# basic_pos_neg_v0001.net
KiCad netlist of a schematic drawn in EAGLE
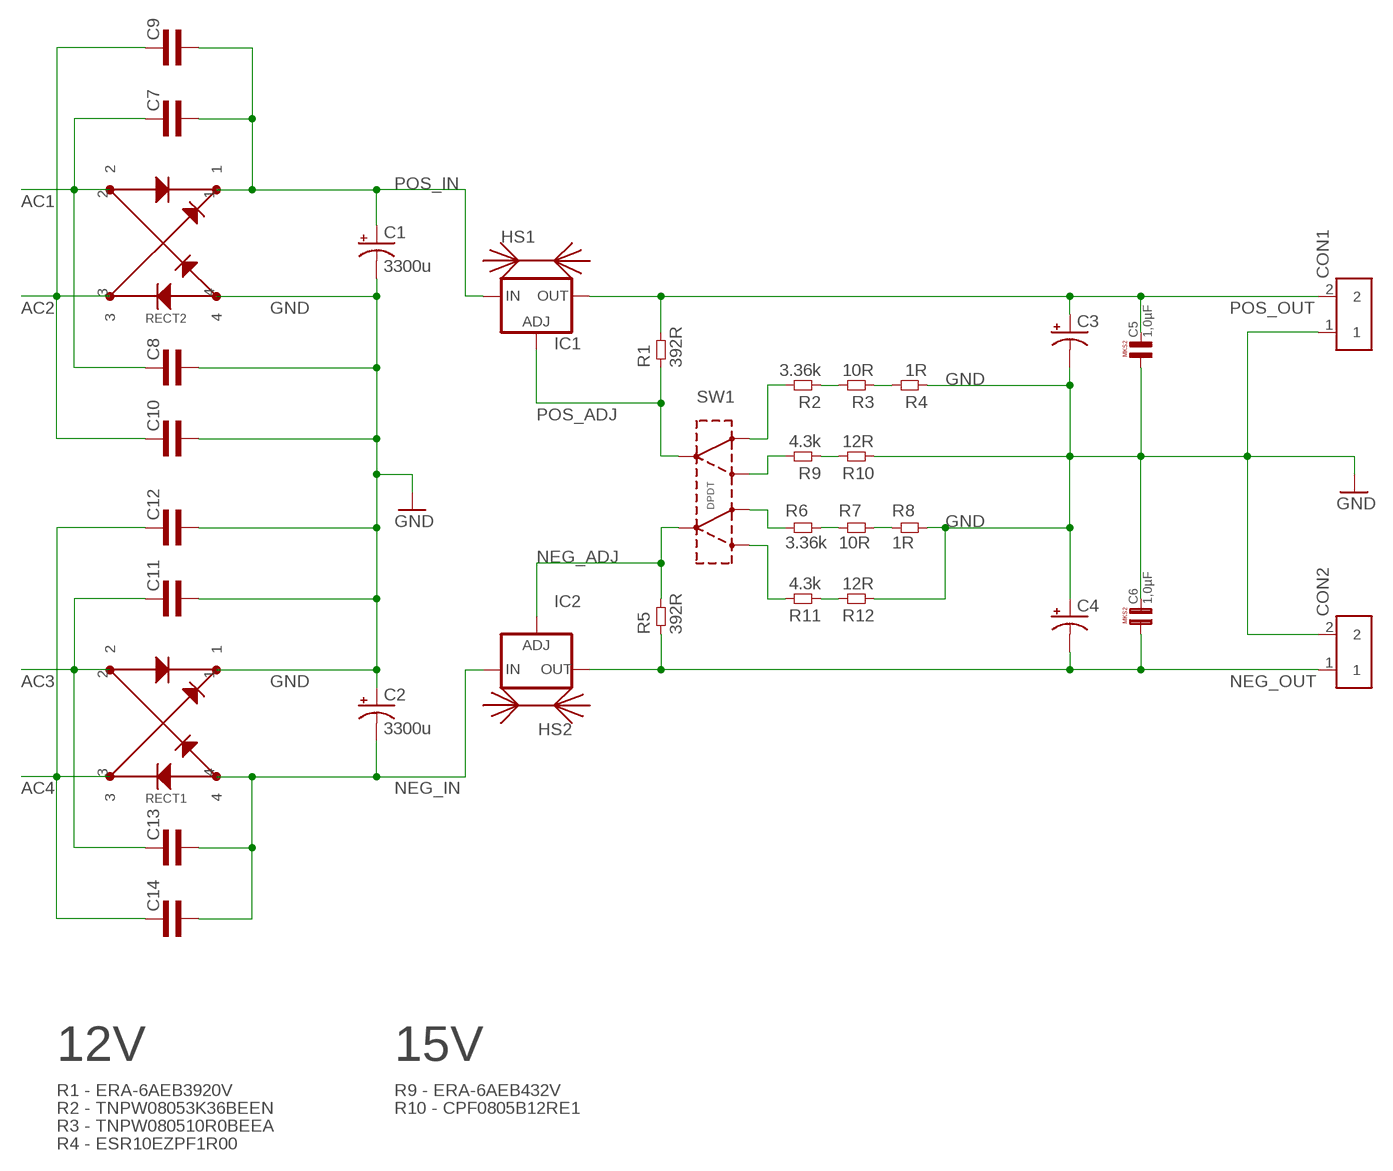
[diagram p0: schematic, sheet 1]

(export (version "E")
  (design (tool "Eeschema 10.0.6"))
  (components
    (comp (ref "C1")
      (value "3300u")
      (footprint "eagle-import:E7,5-18")
      (libsource (lib "eagle-import") (part "CPOL-USE7.5-18"))
    )
    (comp (ref "C2")
      (value "3300u")
      (footprint "eagle-import:E7,5-18")
      (libsource (lib "eagle-import") (part "CPOL-USE7.5-18"))
    )
    (comp (ref "C3")
      (value "CPOL-USE3.5-8")
      (footprint "eagle-import:E3,5-8")
      (libsource (lib "eagle-import") (part "CPOL-USE3.5-8"))
    )
    (comp (ref "C4")
      (value "CPOL-USE3.5-8")
      (footprint "eagle-import:E3,5-8")
      (libsource (lib "eagle-import") (part "CPOL-USE3.5-8"))
    )
    (comp (ref "C5")
      (value "1,0µF")
      (footprint "eagle-import:R5B5")
      (libsource (lib "eagle-import") (part "1,0µF"))
    )
    (comp (ref "C6")
      (value "1,0µF")
      (footprint "eagle-import:R5B5")
      (libsource (lib "eagle-import") (part "1,0µF"))
    )
    (comp (ref "C7")
      (value "CAP0805L3")
      (footprint "eagle-import:0805L3")
      (libsource (lib "eagle-import") (part "CAP0805L3"))
    )
    (comp (ref "C8")
      (value "CAP0805L3")
      (footprint "eagle-import:0805L3")
      (libsource (lib "eagle-import") (part "CAP0805L3"))
    )
    (comp (ref "C9")
      (value "CAP0805L3")
      (footprint "eagle-import:0805L3")
      (libsource (lib "eagle-import") (part "CAP0805L3"))
    )
    (comp (ref "C10")
      (value "CAP0805L3")
      (footprint "eagle-import:0805L3")
      (libsource (lib "eagle-import") (part "CAP0805L3"))
    )
    (comp (ref "C11")
      (value "CAP0805L3")
      (footprint "eagle-import:0805L3")
      (libsource (lib "eagle-import") (part "CAP0805L3"))
    )
    (comp (ref "C12")
      (value "CAP0805L3")
      (footprint "eagle-import:0805L3")
      (libsource (lib "eagle-import") (part "CAP0805L3"))
    )
    (comp (ref "C13")
      (value "CAP0805L3")
      (footprint "eagle-import:0805L3")
      (libsource (lib "eagle-import") (part "CAP0805L3"))
    )
    (comp (ref "C14")
      (value "CAP0805L3")
      (footprint "eagle-import:0805L3")
      (libsource (lib "eagle-import") (part "CAP0805L3"))
    )
    (comp (ref "CON1")
      (value "TERM_BLOCK_2")
      (footprint "eagle-import:TERM_BLOCK_2")
      (libsource (lib "eagle-import") (part "TERM_BLOCK_2"))
    )
    (comp (ref "CON2")
      (value "TERM_BLOCK_2")
      (footprint "eagle-import:TERM_BLOCK_2")
      (libsource (lib "eagle-import") (part "TERM_BLOCK_2"))
    )
    (comp (ref "HS1")
      (value "HEATSINKTO-220-R")
      (footprint "eagle-import:HEATSINK-TO-220-R")
      (libsource (lib "eagle-import") (part "HEATSINKTO-220-R"))
    )
    (comp (ref "HS2")
      (value "HEATSINKTO-220-R")
      (footprint "eagle-import:HEATSINK-TO-220-R")
      (libsource (lib "eagle-import") (part "HEATSINKTO-220-R"))
    )
    (comp (ref "IC1")
      (value "LM317TS")
      (footprint "eagle-import:317TS")
      (libsource (lib "eagle-import") (part "LM317TS"))
    )
    (comp (ref "IC2")
      (value "LM337TS")
      (footprint "eagle-import:337TS")
      (libsource (lib "eagle-import") (part "LM337TS"))
    )
    (comp (ref "R1")
      (value "392R")
      (footprint "eagle-import:0805L3")
      (libsource (lib "eagle-import") (part "RES0805L3"))
    )
    (comp (ref "R2")
      (value "3.36k")
      (footprint "eagle-import:0805L3")
      (libsource (lib "eagle-import") (part "RES0805L3"))
    )
    (comp (ref "R3")
      (value "10R")
      (footprint "eagle-import:0805L3")
      (libsource (lib "eagle-import") (part "RES0805L3"))
    )
    (comp (ref "R4")
      (value "1R")
      (footprint "eagle-import:0805L3")
      (libsource (lib "eagle-import") (part "RES0805L3"))
    )
    (comp (ref "R5")
      (value "392R")
      (footprint "eagle-import:0805L3")
      (libsource (lib "eagle-import") (part "RES0805L3"))
    )
    (comp (ref "R6")
      (value "3.36k")
      (footprint "eagle-import:0805L3")
      (libsource (lib "eagle-import") (part "RES0805L3"))
    )
    (comp (ref "R7")
      (value "10R")
      (footprint "eagle-import:0805L3")
      (libsource (lib "eagle-import") (part "RES0805L3"))
    )
    (comp (ref "R8")
      (value "1R")
      (footprint "eagle-import:0805L3")
      (libsource (lib "eagle-import") (part "RES0805L3"))
    )
    (comp (ref "R9")
      (value "4.3k")
      (footprint "eagle-import:0805L3")
      (libsource (lib "eagle-import") (part "RES0805L3"))
    )
    (comp (ref "R10")
      (value "12R")
      (footprint "eagle-import:0805L3")
      (libsource (lib "eagle-import") (part "RES0805L3"))
    )
    (comp (ref "R11")
      (value "4.3k")
      (footprint "eagle-import:0805L3")
      (libsource (lib "eagle-import") (part "RES0805L3"))
    )
    (comp (ref "R12")
      (value "12R")
      (footprint "eagle-import:0805L3")
      (libsource (lib "eagle-import") (part "RES0805L3"))
    )
    (comp (ref "RECT1")
      (value "RECTIFIER_Z4GP206")
      (footprint "eagle-import:RECTIFIER_ABS-4")
      (libsource (lib "eagle-import") (part "RECTIFIER_Z4GP206"))
    )
    (comp (ref "RECT2")
      (value "RECTIFIER_Z4GP206")
      (footprint "eagle-import:RECTIFIER_ABS-4")
      (libsource (lib "eagle-import") (part "RECTIFIER_Z4GP206"))
    )
    (comp (ref "SW1")
      (value "DPDT")
      (footprint "eagle-import:WIRES-2X6-14G")
      (libsource (lib "eagle-import") (part "DPDT"))
    )
  )
  (nets
    (net (code "1") (name "/AC1") (class "Default")
      (node (ref "C7") (pin "1") (pinfunction "1_1") (pintype "bidirectional"))
      (node (ref "C8") (pin "1") (pinfunction "1_1") (pintype "bidirectional"))
      (node (ref "RECT2") (pin "2") (pinfunction "2_2") (pintype "bidirectional"))
    )
    (net (code "2") (name "/AC2") (class "Default")
      (node (ref "C10") (pin "1") (pinfunction "1_1") (pintype "bidirectional"))
      (node (ref "C9") (pin "1") (pinfunction "1_1") (pintype "bidirectional"))
      (node (ref "RECT2") (pin "3") (pinfunction "3_3") (pintype "bidirectional"))
    )
    (net (code "3") (name "/AC3") (class "Default")
      (node (ref "C11") (pin "1") (pinfunction "1_1") (pintype "bidirectional"))
      (node (ref "C13") (pin "1") (pinfunction "1_1") (pintype "bidirectional"))
      (node (ref "RECT1") (pin "2") (pinfunction "2_2") (pintype "bidirectional"))
    )
    (net (code "4") (name "/AC4") (class "Default")
      (node (ref "C12") (pin "1") (pinfunction "1_1") (pintype "bidirectional"))
      (node (ref "C14") (pin "1") (pinfunction "1_1") (pintype "bidirectional"))
      (node (ref "RECT1") (pin "3") (pinfunction "3_3") (pintype "bidirectional"))
    )
    (net (code "5") (name "/NEG_ADJ") (class "Default")
      (node (ref "IC2") (pin "1") (pinfunction "ADJ_1") (pintype "input"))
      (node (ref "R5") (pin "2") (pinfunction "2_2") (pintype "bidirectional"))
      (node (ref "SW1") (pin "5") (pinfunction "INB_5") (pintype "bidirectional"))
    )
    (net (code "6") (name "/NEG_IN") (class "Default")
      (node (ref "C13") (pin "2") (pinfunction "2_2") (pintype "bidirectional"))
      (node (ref "C14") (pin "2") (pinfunction "2_2") (pintype "bidirectional"))
      (node (ref "C2") (pin "-") (pinfunction "-_-") (pintype "passive"))
      (node (ref "IC2") (pin "2") (pinfunction "IN_2") (pintype "input"))
      (node (ref "RECT1") (pin "4") (pinfunction "4_4") (pintype "bidirectional"))
    )
    (net (code "7") (name "/NEG_OUT") (class "Default")
      (node (ref "C4") (pin "-") (pinfunction "-_-") (pintype "passive"))
      (node (ref "C6") (pin "1") (pinfunction "1_1") (pintype "passive"))
      (node (ref "CON2") (pin "1") (pinfunction "1_1") (pintype "bidirectional"))
      (node (ref "IC2") (pin "3") (pinfunction "OUT_3") (pintype "passive"))
      (node (ref "R5") (pin "1") (pinfunction "1_1") (pintype "bidirectional"))
    )
    (net (code "8") (name "/POS_ADJ") (class "Default")
      (node (ref "IC1") (pin "1") (pinfunction "ADJ_1") (pintype "input"))
      (node (ref "R1") (pin "1") (pinfunction "1_1") (pintype "bidirectional"))
      (node (ref "SW1") (pin "2") (pinfunction "INA_2") (pintype "bidirectional"))
    )
    (net (code "9") (name "/POS_IN") (class "Default")
      (node (ref "C1") (pin "+") (pinfunction "+_+") (pintype "passive"))
      (node (ref "C7") (pin "2") (pinfunction "2_2") (pintype "bidirectional"))
      (node (ref "C9") (pin "2") (pinfunction "2_2") (pintype "bidirectional"))
      (node (ref "IC1") (pin "3") (pinfunction "IN_3") (pintype "input"))
      (node (ref "RECT2") (pin "1") (pinfunction "1_1") (pintype "bidirectional"))
    )
    (net (code "10") (name "/POS_OUT") (class "Default")
      (node (ref "C3") (pin "+") (pinfunction "+_+") (pintype "passive"))
      (node (ref "C5") (pin "2") (pinfunction "2_2") (pintype "passive"))
      (node (ref "CON1") (pin "2") (pinfunction "2_2") (pintype "bidirectional"))
      (node (ref "IC1") (pin "2") (pinfunction "OUT_2") (pintype "passive"))
      (node (ref "R1") (pin "2") (pinfunction "2_2") (pintype "bidirectional"))
    )
    (net (code "11") (name "GND") (class "Default")
      (node (ref "C1") (pin "-") (pinfunction "-_-") (pintype "passive"))
      (node (ref "C10") (pin "2") (pinfunction "2_2") (pintype "bidirectional"))
      (node (ref "C11") (pin "2") (pinfunction "2_2") (pintype "bidirectional"))
      (node (ref "C12") (pin "2") (pinfunction "2_2") (pintype "bidirectional"))
      (node (ref "C2") (pin "+") (pinfunction "+_+") (pintype "passive"))
      (node (ref "C3") (pin "-") (pinfunction "-_-") (pintype "passive"))
      (node (ref "C4") (pin "+") (pinfunction "+_+") (pintype "passive"))
      (node (ref "C5") (pin "1") (pinfunction "1_1") (pintype "passive"))
      (node (ref "C6") (pin "2") (pinfunction "2_2") (pintype "passive"))
      (node (ref "C8") (pin "2") (pinfunction "2_2") (pintype "bidirectional"))
      (node (ref "CON1") (pin "1") (pinfunction "1_1") (pintype "bidirectional"))
      (node (ref "CON2") (pin "2") (pinfunction "2_2") (pintype "bidirectional"))
      (node (ref "R10") (pin "1") (pinfunction "1_1") (pintype "bidirectional"))
      (node (ref "R12") (pin "1") (pinfunction "1_1") (pintype "bidirectional"))
      (node (ref "R4") (pin "1") (pinfunction "1_1") (pintype "bidirectional"))
      (node (ref "R8") (pin "2") (pinfunction "2_2") (pintype "bidirectional"))
      (node (ref "RECT1") (pin "1") (pinfunction "1_1") (pintype "bidirectional"))
      (node (ref "RECT2") (pin "4") (pinfunction "4_4") (pintype "bidirectional"))
    )
    (net (code "12") (name "Net-(R2-Pad1)") (class "Default")
      (node (ref "R2") (pin "1") (pinfunction "1_1") (pintype "bidirectional"))
      (node (ref "R3") (pin "2") (pinfunction "2_2") (pintype "bidirectional"))
    )
    (net (code "13") (name "Net-(R3-Pad1)") (class "Default")
      (node (ref "R3") (pin "1") (pinfunction "1_1") (pintype "bidirectional"))
      (node (ref "R4") (pin "2") (pinfunction "2_2") (pintype "bidirectional"))
    )
    (net (code "14") (name "Net-(R6-Pad2)") (class "Default")
      (node (ref "R6") (pin "2") (pinfunction "2_2") (pintype "bidirectional"))
      (node (ref "R7") (pin "1") (pinfunction "1_1") (pintype "bidirectional"))
    )
    (net (code "15") (name "Net-(R7-Pad2)") (class "Default")
      (node (ref "R7") (pin "2") (pinfunction "2_2") (pintype "bidirectional"))
      (node (ref "R8") (pin "1") (pinfunction "1_1") (pintype "bidirectional"))
    )
    (net (code "16") (name "Net-(R10-Pad2)") (class "Default")
      (node (ref "R10") (pin "2") (pinfunction "2_2") (pintype "bidirectional"))
      (node (ref "R9") (pin "1") (pinfunction "1_1") (pintype "bidirectional"))
    )
    (net (code "17") (name "Net-(R11-Pad1)") (class "Default")
      (node (ref "R11") (pin "1") (pinfunction "1_1") (pintype "bidirectional"))
      (node (ref "R12") (pin "2") (pinfunction "2_2") (pintype "bidirectional"))
    )
    (net (code "18") (name "Net-(SW1-OUTA1)") (class "Default")
      (node (ref "R2") (pin "2") (pinfunction "2_2") (pintype "bidirectional"))
      (node (ref "SW1") (pin "1") (pinfunction "OUTA1_1") (pintype "bidirectional"))
    )
    (net (code "19") (name "Net-(SW1-OUTA2)") (class "Default")
      (node (ref "R9") (pin "2") (pinfunction "2_2") (pintype "bidirectional"))
      (node (ref "SW1") (pin "3") (pinfunction "OUTA2_3") (pintype "bidirectional"))
    )
    (net (code "20") (name "Net-(SW1-OUTB1)") (class "Default")
      (node (ref "R6") (pin "1") (pinfunction "1_1") (pintype "bidirectional"))
      (node (ref "SW1") (pin "6") (pinfunction "OUTB1_6") (pintype "bidirectional"))
    )
    (net (code "21") (name "Net-(SW1-OUTB2)") (class "Default")
      (node (ref "R11") (pin "2") (pinfunction "2_2") (pintype "bidirectional"))
      (node (ref "SW1") (pin "4") (pinfunction "OUTB2_4") (pintype "bidirectional"))
    )
  )
)
